# Sheet_Hall_sensor.net
KiCad netlist of a schematic drawn in Altium Designer
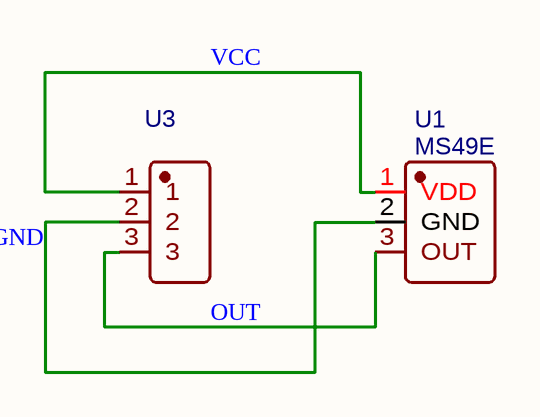
[diagram p0: Sheet_Hall sensor.schdoc]

(export (version "E")
  (design (tool "Eeschema 10.0.6"))
  (components
    (comp (ref "U1")
      (value "MS49E")
      (fields (field (name "MANUFACTURER") "杭州瑞盟") (field (name "CONTRIBUTOR") "LCSC"))
      (libsource (lib "altium-import") (part "root_0_MS49E_"))
    )
    (comp (ref "U3")
      (value "WAFER-PH2.0-3PZZ-R62")
      (fields (field (name "MANUFACTURER") "XUNPU(讯普)") (field (name "CONTRIBUTOR") "lcsc"))
      (libsource (lib "altium-import") (part "root_0_WAFER-PH2.0-3PZZ-R62_"))
    )
  )
  (nets
    (net (code "1") (name "/GND") (class "Default")
      (node (ref "U1") (pin "2") (pinfunction "GND_2") (pintype "passive"))
      (node (ref "U3") (pin "2") (pinfunction "2_2") (pintype "passive"))
    )
    (net (code "2") (name "/OUT") (class "Default")
      (node (ref "U1") (pin "3") (pinfunction "OUT_3") (pintype "passive"))
      (node (ref "U3") (pin "3") (pinfunction "3_3") (pintype "passive"))
    )
    (net (code "3") (name "/VCC") (class "Default")
      (node (ref "U1") (pin "1") (pinfunction "VDD_1") (pintype "passive"))
      (node (ref "U3") (pin "1") (pinfunction "1_1") (pintype "passive"))
    )
  )
)
